# CT-Keypad-Rev4.net
KiCad netlist of a schematic drawn in EAGLE
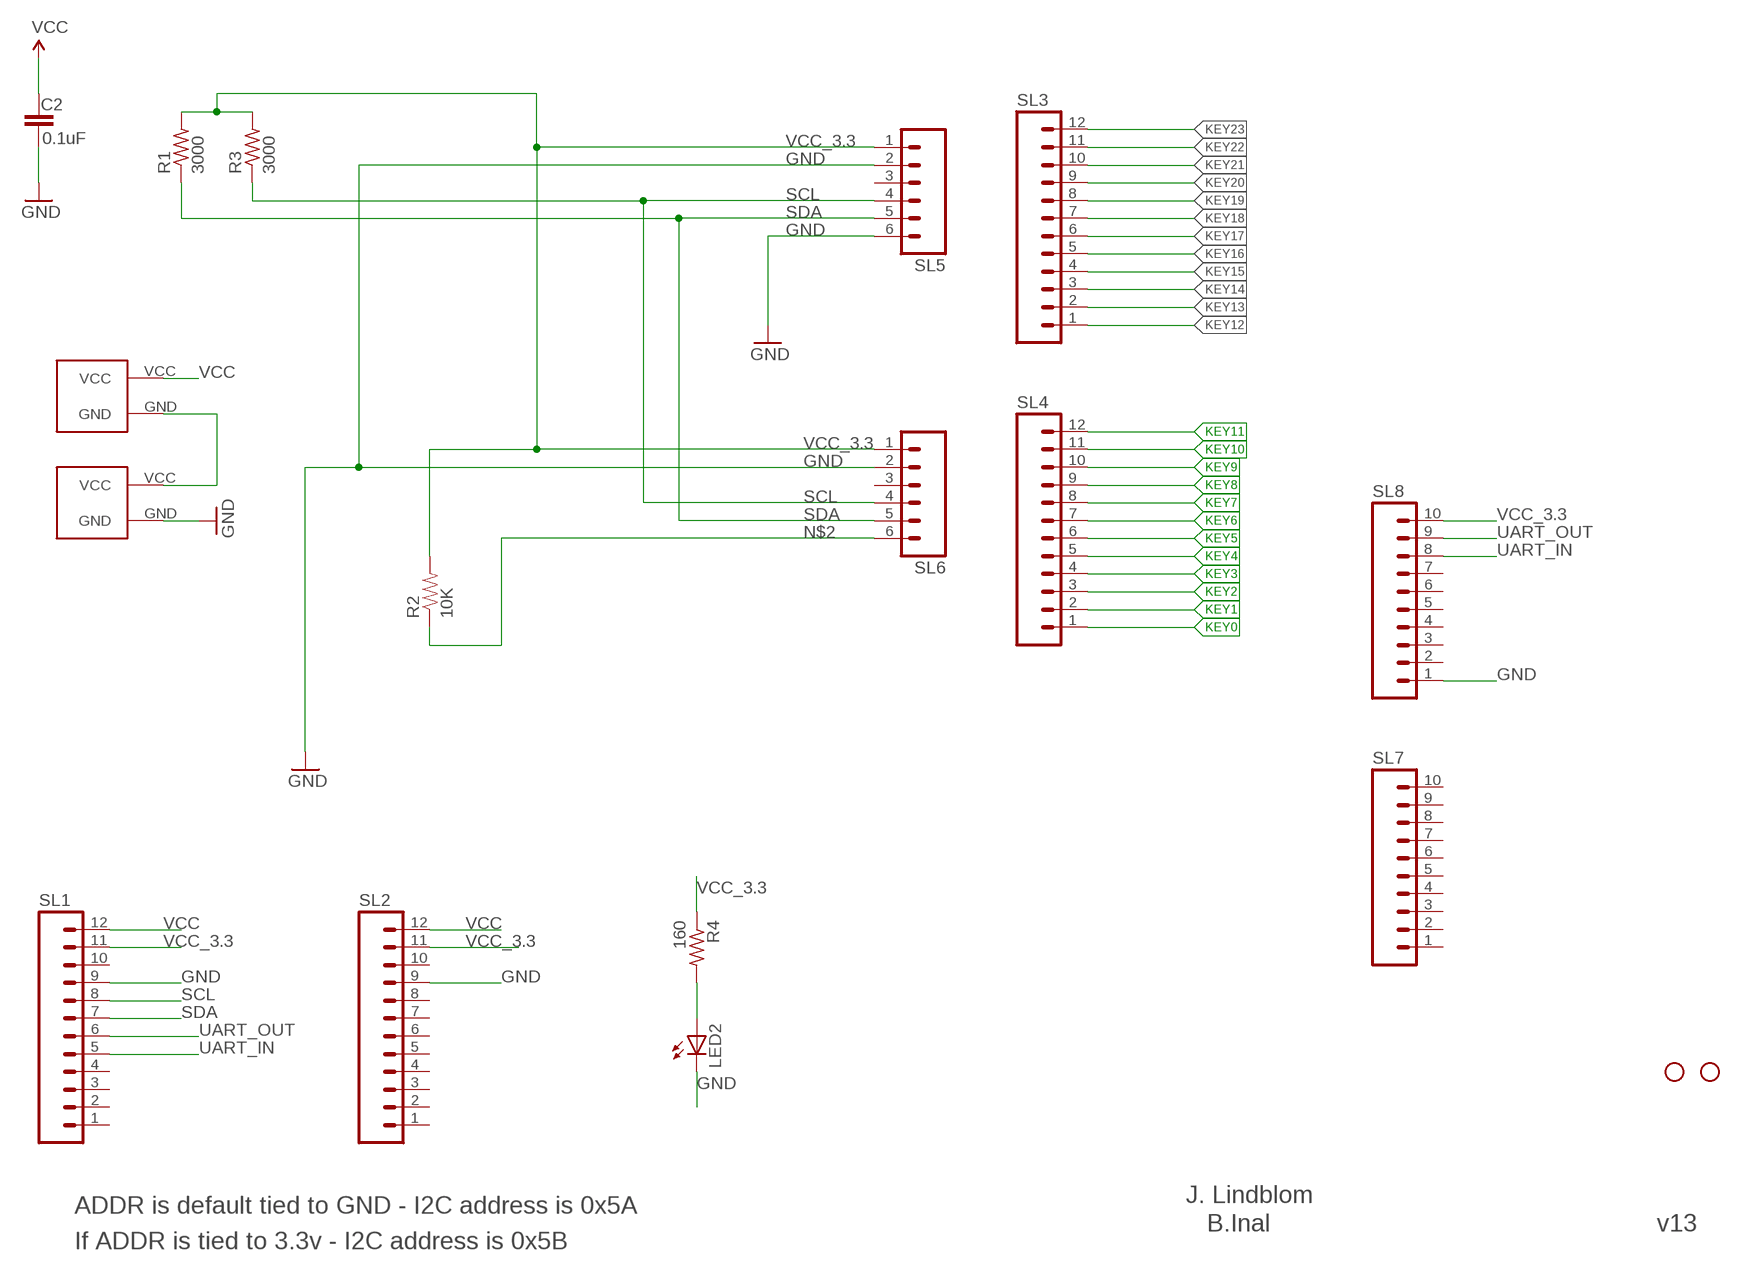
[diagram p0: schematic, sheet 1]

(export (version "E")
  (design (tool "Eeschema 10.0.6"))
  (components
    (comp (ref "C2")
      (value "0.1uF")
      (footprint "eagle-import:0603-CAP")
      (libsource (lib "eagle-import") (part "0.1UF-25V(+80/-20%)(0603)"))
    )
    (comp (ref "JP3")
      (value "STAND-OFF")
      (footprint "eagle-import:STAND-OFF")
      (libsource (lib "eagle-import") (part "STAND-OFF"))
    )
    (comp (ref "JP4")
      (value "STAND-OFF")
      (footprint "eagle-import:STAND-OFF")
      (libsource (lib "eagle-import") (part "STAND-OFF"))
    )
    (comp (ref "LED2")
      (value "LEDCHIPLED_0805")
      (footprint "eagle-import:CHIPLED_0805")
      (libsource (lib "eagle-import") (part "LEDCHIPLED_0805"))
    )
    (comp (ref "R1")
      (value "3000")
      (footprint "eagle-import:R0603")
      (libsource (lib "eagle-import") (part "R-US_R0603"))
    )
    (comp (ref "R2")
      (value "10K")
      (footprint "eagle-import:0603-RES")
      (libsource (lib "eagle-import") (part "10KOHM1/10W1%(0603)0603"))
    )
    (comp (ref "R3")
      (value "3000")
      (footprint "eagle-import:R0603")
      (libsource (lib "eagle-import") (part "R-US_R0603"))
    )
    (comp (ref "R4")
      (value "160")
      (footprint "eagle-import:R0603")
      (libsource (lib "eagle-import") (part "R-US_R0603"))
    )
    (comp (ref "SL1")
      (value "M12")
      (footprint "eagle-import:12P")
      (libsource (lib "eagle-import") (part "M12"))
    )
    (comp (ref "SL2")
      (value "M12")
      (footprint "eagle-import:12P")
      (libsource (lib "eagle-import") (part "M12"))
    )
    (comp (ref "SL3")
      (value "M12")
      (footprint "eagle-import:12P")
      (fields (field (name "OC_FARNELL") "unknown") (field (name "OC_NEWARK") "unknown"))
      (libsource (lib "eagle-import") (part "M12"))
    )
    (comp (ref "SL4")
      (value "M12")
      (footprint "eagle-import:12P")
      (fields (field (name "OC_FARNELL") "unknown") (field (name "OC_NEWARK") "unknown"))
      (libsource (lib "eagle-import") (part "M12"))
    )
    (comp (ref "SL5")
      (value "M06")
      (footprint "eagle-import:06P")
      (libsource (lib "eagle-import") (part "M06"))
    )
    (comp (ref "SL6")
      (value "M06")
      (footprint "eagle-import:06P")
      (libsource (lib "eagle-import") (part "M06"))
    )
    (comp (ref "SL7")
      (value "M10")
      (footprint "eagle-import:10P")
      (libsource (lib "eagle-import") (part "M10"))
    )
    (comp (ref "SL8")
      (value "M10")
      (footprint "eagle-import:10P")
      (libsource (lib "eagle-import") (part "M10"))
    )
    (comp (ref "U$1")
      (value "BATTERY")
      (footprint "eagle-import:BATTERY")
      (libsource (lib "eagle-import") (part "BATTERY"))
    )
    (comp (ref "U$2")
      (value "BATTERY")
      (footprint "eagle-import:BATTERY")
      (libsource (lib "eagle-import") (part "BATTERY"))
    )
  )
  (nets
    (net (code "1") (name "/N$2") (class "Default")
      (node (ref "R2") (pin "1") (pinfunction "1_1") (pintype "passive"))
      (node (ref "SL6") (pin "6") (pinfunction "6_6") (pintype "passive"))
    )
    (net (code "2") (name "/SCL") (class "Default")
      (node (ref "R3") (pin "1") (pinfunction "1_1") (pintype "passive"))
      (node (ref "SL1") (pin "8") (pinfunction "8_8") (pintype "passive"))
      (node (ref "SL5") (pin "4") (pinfunction "4_4") (pintype "passive"))
      (node (ref "SL6") (pin "4") (pinfunction "4_4") (pintype "passive"))
    )
    (net (code "3") (name "/SDA") (class "Default")
      (node (ref "R1") (pin "1") (pinfunction "1_1") (pintype "passive"))
      (node (ref "SL1") (pin "7") (pinfunction "7_7") (pintype "passive"))
      (node (ref "SL5") (pin "5") (pinfunction "5_5") (pintype "passive"))
      (node (ref "SL6") (pin "5") (pinfunction "5_5") (pintype "passive"))
    )
    (net (code "4") (name "/UART_IN") (class "Default")
      (node (ref "SL1") (pin "5") (pinfunction "5_5") (pintype "passive"))
      (node (ref "SL8") (pin "8") (pinfunction "8_8") (pintype "passive"))
    )
    (net (code "5") (name "/UART_OUT") (class "Default")
      (node (ref "SL1") (pin "6") (pinfunction "6_6") (pintype "passive"))
      (node (ref "SL8") (pin "9") (pinfunction "9_9") (pintype "passive"))
    )
    (net (code "6") (name "/VCC_3.3") (class "Default")
      (node (ref "R1") (pin "2") (pinfunction "2_2") (pintype "passive"))
      (node (ref "R2") (pin "2") (pinfunction "2_2") (pintype "passive"))
      (node (ref "R3") (pin "2") (pinfunction "2_2") (pintype "passive"))
      (node (ref "R4") (pin "1") (pinfunction "1_1") (pintype "passive"))
      (node (ref "SL1") (pin "11") (pinfunction "11_11") (pintype "passive"))
      (node (ref "SL2") (pin "11") (pinfunction "11_11") (pintype "passive"))
      (node (ref "SL5") (pin "1") (pinfunction "1_1") (pintype "passive"))
      (node (ref "SL6") (pin "1") (pinfunction "1_1") (pintype "passive"))
      (node (ref "SL8") (pin "10") (pinfunction "10_10") (pintype "passive"))
    )
    (net (code "7") (name "GND") (class "Default")
      (node (ref "C2") (pin "2") (pinfunction "2_2") (pintype "passive"))
      (node (ref "LED2") (pin "C") (pinfunction "C_C") (pintype "passive"))
      (node (ref "SL1") (pin "9") (pinfunction "9_9") (pintype "passive"))
      (node (ref "SL2") (pin "9") (pinfunction "9_9") (pintype "passive"))
      (node (ref "SL5") (pin "2") (pinfunction "2_2") (pintype "passive"))
      (node (ref "SL5") (pin "6") (pinfunction "6_6") (pintype "passive"))
      (node (ref "SL6") (pin "2") (pinfunction "2_2") (pintype "passive"))
      (node (ref "SL8") (pin "1") (pinfunction "1_1") (pintype "passive"))
      (node (ref "U$2") (pin "GND") (pinfunction "GND_GND") (pintype "power_in"))
    )
    (net (code "8") (name "KEY0") (class "Default")
      (node (ref "SL4") (pin "1") (pinfunction "1_1") (pintype "passive"))
    )
    (net (code "9") (name "KEY1") (class "Default")
      (node (ref "SL4") (pin "2") (pinfunction "2_2") (pintype "passive"))
    )
    (net (code "10") (name "KEY2") (class "Default")
      (node (ref "SL4") (pin "3") (pinfunction "3_3") (pintype "passive"))
    )
    (net (code "11") (name "KEY3") (class "Default")
      (node (ref "SL4") (pin "4") (pinfunction "4_4") (pintype "passive"))
    )
    (net (code "12") (name "KEY4") (class "Default")
      (node (ref "SL4") (pin "5") (pinfunction "5_5") (pintype "passive"))
    )
    (net (code "13") (name "KEY5") (class "Default")
      (node (ref "SL4") (pin "6") (pinfunction "6_6") (pintype "passive"))
    )
    (net (code "14") (name "KEY6") (class "Default")
      (node (ref "SL4") (pin "7") (pinfunction "7_7") (pintype "passive"))
    )
    (net (code "15") (name "KEY7") (class "Default")
      (node (ref "SL4") (pin "8") (pinfunction "8_8") (pintype "passive"))
    )
    (net (code "16") (name "KEY8") (class "Default")
      (node (ref "SL4") (pin "9") (pinfunction "9_9") (pintype "passive"))
    )
    (net (code "17") (name "KEY9") (class "Default")
      (node (ref "SL4") (pin "10") (pinfunction "10_10") (pintype "passive"))
    )
    (net (code "18") (name "KEY10") (class "Default")
      (node (ref "SL4") (pin "11") (pinfunction "11_11") (pintype "passive"))
    )
    (net (code "19") (name "KEY11") (class "Default")
      (node (ref "SL4") (pin "12") (pinfunction "12_12") (pintype "passive"))
    )
    (net (code "20") (name "KEY12") (class "Default")
      (node (ref "SL3") (pin "1") (pinfunction "1_1") (pintype "passive"))
    )
    (net (code "21") (name "KEY13") (class "Default")
      (node (ref "SL3") (pin "2") (pinfunction "2_2") (pintype "passive"))
    )
    (net (code "22") (name "KEY14") (class "Default")
      (node (ref "SL3") (pin "3") (pinfunction "3_3") (pintype "passive"))
    )
    (net (code "23") (name "KEY15") (class "Default")
      (node (ref "SL3") (pin "4") (pinfunction "4_4") (pintype "passive"))
    )
    (net (code "24") (name "KEY16") (class "Default")
      (node (ref "SL3") (pin "5") (pinfunction "5_5") (pintype "passive"))
    )
    (net (code "25") (name "KEY17") (class "Default")
      (node (ref "SL3") (pin "6") (pinfunction "6_6") (pintype "passive"))
    )
    (net (code "26") (name "KEY18") (class "Default")
      (node (ref "SL3") (pin "7") (pinfunction "7_7") (pintype "passive"))
    )
    (net (code "27") (name "KEY19") (class "Default")
      (node (ref "SL3") (pin "8") (pinfunction "8_8") (pintype "passive"))
    )
    (net (code "28") (name "KEY20") (class "Default")
      (node (ref "SL3") (pin "9") (pinfunction "9_9") (pintype "passive"))
    )
    (net (code "29") (name "KEY21") (class "Default")
      (node (ref "SL3") (pin "10") (pinfunction "10_10") (pintype "passive"))
    )
    (net (code "30") (name "KEY22") (class "Default")
      (node (ref "SL3") (pin "11") (pinfunction "11_11") (pintype "passive"))
    )
    (net (code "31") (name "KEY23") (class "Default")
      (node (ref "SL3") (pin "12") (pinfunction "12_12") (pintype "passive"))
    )
    (net (code "32") (name "Net-(LED2-PadA)") (class "Default")
      (node (ref "LED2") (pin "A") (pinfunction "A_A") (pintype "passive"))
      (node (ref "R4") (pin "2") (pinfunction "2_2") (pintype "passive"))
    )
    (net (code "33") (name "Net-(U$1-PadGND)") (class "Default")
      (node (ref "U$1") (pin "GND") (pinfunction "GND_GND") (pintype "power_in"))
      (node (ref "U$2") (pin "VCC") (pinfunction "VCC_VCC") (pintype "power_in"))
    )
    (net (code "34") (name "VCC") (class "Default")
      (node (ref "C2") (pin "1") (pinfunction "1_1") (pintype "passive"))
      (node (ref "SL1") (pin "12") (pinfunction "12_12") (pintype "passive"))
      (node (ref "SL2") (pin "12") (pinfunction "12_12") (pintype "passive"))
      (node (ref "U$1") (pin "VCC") (pinfunction "VCC_VCC") (pintype "power_in"))
    )
    (net (code "35") (name "unconnected-(SL1-Pad1)") (class "Default")
      (node (ref "SL1") (pin "1") (pinfunction "1_1") (pintype "passive"))
    )
    (net (code "36") (name "unconnected-(SL1-Pad2)") (class "Default")
      (node (ref "SL1") (pin "2") (pinfunction "2_2") (pintype "passive"))
    )
    (net (code "37") (name "unconnected-(SL1-Pad3)") (class "Default")
      (node (ref "SL1") (pin "3") (pinfunction "3_3") (pintype "passive"))
    )
    (net (code "38") (name "unconnected-(SL1-Pad4)") (class "Default")
      (node (ref "SL1") (pin "4") (pinfunction "4_4") (pintype "passive"))
    )
    (net (code "39") (name "unconnected-(SL1-Pad10)") (class "Default")
      (node (ref "SL1") (pin "10") (pinfunction "10_10") (pintype "passive"))
    )
    (net (code "40") (name "unconnected-(SL2-Pad1)") (class "Default")
      (node (ref "SL2") (pin "1") (pinfunction "1_1") (pintype "passive"))
    )
    (net (code "41") (name "unconnected-(SL2-Pad2)") (class "Default")
      (node (ref "SL2") (pin "2") (pinfunction "2_2") (pintype "passive"))
    )
    (net (code "42") (name "unconnected-(SL2-Pad3)") (class "Default")
      (node (ref "SL2") (pin "3") (pinfunction "3_3") (pintype "passive"))
    )
    (net (code "43") (name "unconnected-(SL2-Pad4)") (class "Default")
      (node (ref "SL2") (pin "4") (pinfunction "4_4") (pintype "passive"))
    )
    (net (code "44") (name "unconnected-(SL2-Pad5)") (class "Default")
      (node (ref "SL2") (pin "5") (pinfunction "5_5") (pintype "passive"))
    )
    (net (code "45") (name "unconnected-(SL2-Pad6)") (class "Default")
      (node (ref "SL2") (pin "6") (pinfunction "6_6") (pintype "passive"))
    )
    (net (code "46") (name "unconnected-(SL2-Pad7)") (class "Default")
      (node (ref "SL2") (pin "7") (pinfunction "7_7") (pintype "passive"))
    )
    (net (code "47") (name "unconnected-(SL2-Pad8)") (class "Default")
      (node (ref "SL2") (pin "8") (pinfunction "8_8") (pintype "passive"))
    )
    (net (code "48") (name "unconnected-(SL2-Pad10)") (class "Default")
      (node (ref "SL2") (pin "10") (pinfunction "10_10") (pintype "passive"))
    )
    (net (code "49") (name "unconnected-(SL5-Pad3)") (class "Default")
      (node (ref "SL5") (pin "3") (pinfunction "3_3") (pintype "passive"))
    )
    (net (code "50") (name "unconnected-(SL6-Pad3)") (class "Default")
      (node (ref "SL6") (pin "3") (pinfunction "3_3") (pintype "passive"))
    )
    (net (code "51") (name "unconnected-(SL7-Pad1)") (class "Default")
      (node (ref "SL7") (pin "1") (pinfunction "1_1") (pintype "passive"))
    )
    (net (code "52") (name "unconnected-(SL7-Pad2)") (class "Default")
      (node (ref "SL7") (pin "2") (pinfunction "2_2") (pintype "passive"))
    )
    (net (code "53") (name "unconnected-(SL7-Pad3)") (class "Default")
      (node (ref "SL7") (pin "3") (pinfunction "3_3") (pintype "passive"))
    )
    (net (code "54") (name "unconnected-(SL7-Pad4)") (class "Default")
      (node (ref "SL7") (pin "4") (pinfunction "4_4") (pintype "passive"))
    )
    (net (code "55") (name "unconnected-(SL7-Pad5)") (class "Default")
      (node (ref "SL7") (pin "5") (pinfunction "5_5") (pintype "passive"))
    )
    (net (code "56") (name "unconnected-(SL7-Pad6)") (class "Default")
      (node (ref "SL7") (pin "6") (pinfunction "6_6") (pintype "passive"))
    )
    (net (code "57") (name "unconnected-(SL7-Pad7)") (class "Default")
      (node (ref "SL7") (pin "7") (pinfunction "7_7") (pintype "passive"))
    )
    (net (code "58") (name "unconnected-(SL7-Pad8)") (class "Default")
      (node (ref "SL7") (pin "8") (pinfunction "8_8") (pintype "passive"))
    )
    (net (code "59") (name "unconnected-(SL7-Pad9)") (class "Default")
      (node (ref "SL7") (pin "9") (pinfunction "9_9") (pintype "passive"))
    )
    (net (code "60") (name "unconnected-(SL7-Pad10)") (class "Default")
      (node (ref "SL7") (pin "10") (pinfunction "10_10") (pintype "passive"))
    )
    (net (code "61") (name "unconnected-(SL8-Pad2)") (class "Default")
      (node (ref "SL8") (pin "2") (pinfunction "2_2") (pintype "passive"))
    )
    (net (code "62") (name "unconnected-(SL8-Pad3)") (class "Default")
      (node (ref "SL8") (pin "3") (pinfunction "3_3") (pintype "passive"))
    )
    (net (code "63") (name "unconnected-(SL8-Pad4)") (class "Default")
      (node (ref "SL8") (pin "4") (pinfunction "4_4") (pintype "passive"))
    )
    (net (code "64") (name "unconnected-(SL8-Pad5)") (class "Default")
      (node (ref "SL8") (pin "5") (pinfunction "5_5") (pintype "passive"))
    )
    (net (code "65") (name "unconnected-(SL8-Pad6)") (class "Default")
      (node (ref "SL8") (pin "6") (pinfunction "6_6") (pintype "passive"))
    )
    (net (code "66") (name "unconnected-(SL8-Pad7)") (class "Default")
      (node (ref "SL8") (pin "7") (pinfunction "7_7") (pintype "passive"))
    )
  )
)
